# Mi2_v2.net
KiCad netlist of a schematic drawn in EAGLE
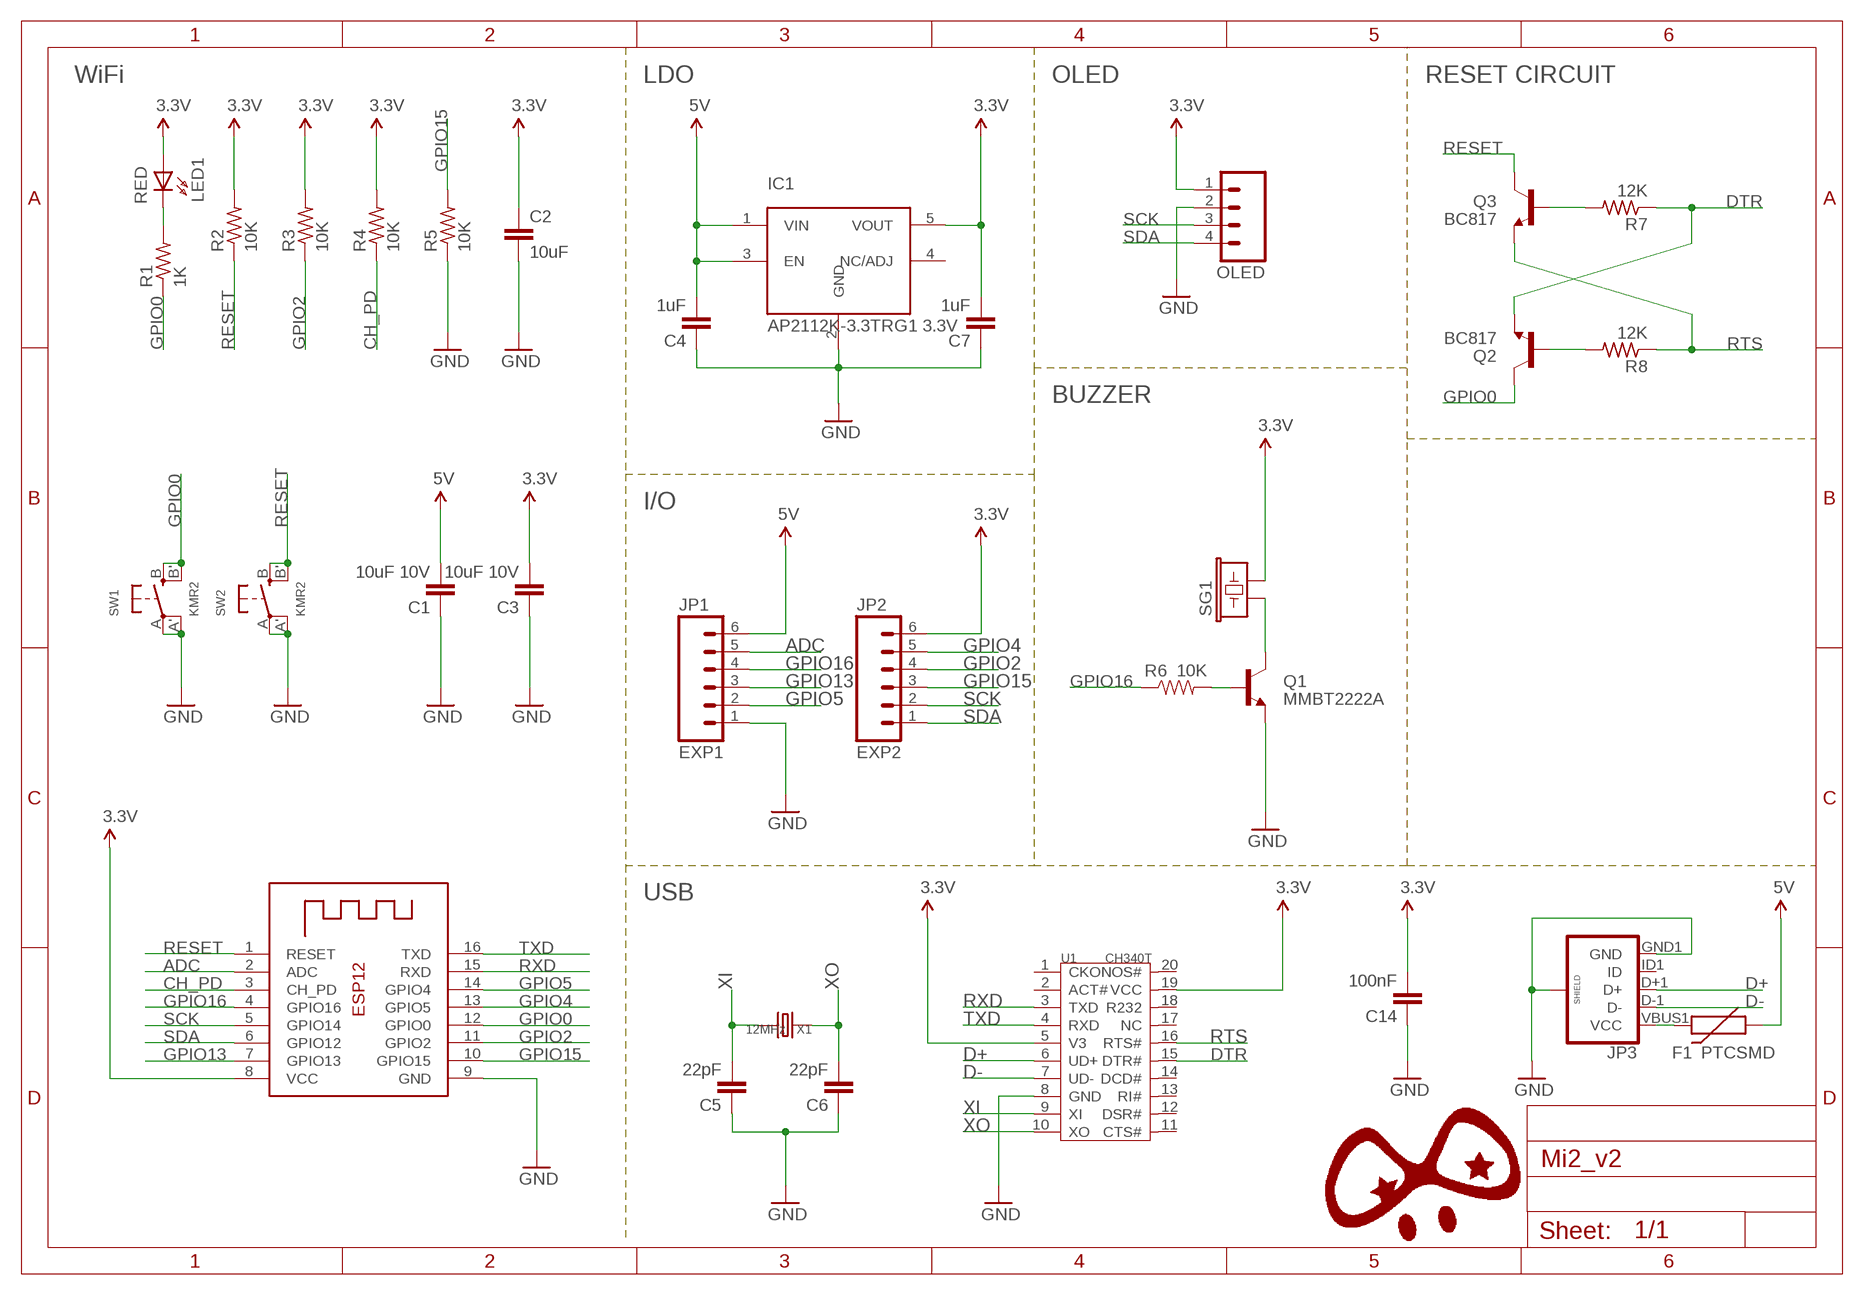
[diagram p0: schematic, sheet 1]

(export (version "E")
  (design (tool "Eeschema 10.0.6"))
  (components
    (comp (ref "C1")
      (value "10uF 10V")
      (footprint "eagle-import:0402-CAP")
      (libsource (lib "eagle-import") (part "CAP0402-CAP"))
    )
    (comp (ref "C2")
      (value "10uF")
      (footprint "eagle-import:0603-CAP")
      (libsource (lib "eagle-import") (part "10UF-6.3V-20%(0603)"))
    )
    (comp (ref "C3")
      (value "10uF 10V")
      (footprint "eagle-import:0402-CAP")
      (libsource (lib "eagle-import") (part "CAP0402-CAP"))
    )
    (comp (ref "C4")
      (value "1uF")
      (footprint "eagle-import:0402-CAP")
      (libsource (lib "eagle-import") (part "CAP0402-CAP"))
    )
    (comp (ref "C5")
      (value "22pF")
      (footprint "eagle-import:0402-CAP")
      (libsource (lib "eagle-import") (part "CAP0402-CAP"))
    )
    (comp (ref "C6")
      (value "22pF")
      (footprint "eagle-import:0402-CAP")
      (libsource (lib "eagle-import") (part "CAP0402-CAP"))
    )
    (comp (ref "C7")
      (value "1uF")
      (footprint "eagle-import:0402-CAP")
      (libsource (lib "eagle-import") (part "CAP0402-CAP"))
    )
    (comp (ref "C14")
      (value "100nF")
      (footprint "eagle-import:0402-CAP")
      (libsource (lib "eagle-import") (part "CAP0402-CAP"))
    )
    (comp (ref "F1")
      (value "PTCSMD")
      (footprint "eagle-import:PTC-1206")
      (libsource (lib "eagle-import") (part "PTCSMD"))
    )
    (comp (ref "IC1")
      (value "AP2112K-3.3TRG1 3.3V")
      (footprint "eagle-import:SOT23-5")
      (libsource (lib "eagle-import") (part "5PIN_REG"))
    )
    (comp (ref "JP1")
      (value "EXP1")
      (footprint "eagle-import:1X06_LOCK")
      (libsource (lib "eagle-import") (part "M06LOCK"))
    )
    (comp (ref "JP2")
      (value "EXP2")
      (footprint "eagle-import:1X06_LOCK")
      (libsource (lib "eagle-import") (part "M06LOCK"))
    )
    (comp (ref "JP3")
      (value "USB_MICROB_PLUGCONN-11752")
      (footprint "eagle-import:USB-B-MICRO-SMD_V03")
      (libsource (lib "eagle-import") (part "USB_MICROB_PLUGCONN-11752"))
    )
    (comp (ref "LED1")
      (value "RED")
      (footprint "eagle-import:LED-0603_L")
      (libsource (lib "eagle-import") (part "LED0603DWS_L"))
    )
    (comp (ref "OLED")
      (value "M04LOCK")
      (footprint "eagle-import:1X04_LOCK")
      (libsource (lib "eagle-import") (part "M04LOCK"))
    )
    (comp (ref "Q1")
      (value "MMBT2222A")
      (footprint "eagle-import:SOT23-3")
      (libsource (lib "eagle-import") (part "TRANSISTOR_NPNMMBT2222A"))
    )
    (comp (ref "Q2")
      (value "BC817")
      (footprint "eagle-import:SOT23-3")
      (libsource (lib "eagle-import") (part "TRANSISTOR_NPNMMBT2222A"))
    )
    (comp (ref "Q3")
      (value "BC817")
      (footprint "eagle-import:SOT23-3")
      (libsource (lib "eagle-import") (part "TRANSISTOR_NPNMMBT2222A"))
    )
    (comp (ref "R1")
      (value "1K")
      (footprint "eagle-import:R0402")
      (libsource (lib "eagle-import") (part "R-US_R0402"))
    )
    (comp (ref "R2")
      (value "10K")
      (footprint "eagle-import:R0402")
      (libsource (lib "eagle-import") (part "R-US_R0402"))
    )
    (comp (ref "R3")
      (value "10K")
      (footprint "eagle-import:R0402")
      (libsource (lib "eagle-import") (part "R-US_R0402"))
    )
    (comp (ref "R4")
      (value "10K")
      (footprint "eagle-import:R0402")
      (libsource (lib "eagle-import") (part "R-US_R0402"))
    )
    (comp (ref "R5")
      (value "10K")
      (footprint "eagle-import:R0402")
      (libsource (lib "eagle-import") (part "R-US_R0402"))
    )
    (comp (ref "R6")
      (value "10K")
      (footprint "eagle-import:0402-RES")
      (libsource (lib "eagle-import") (part "RESISTOR0402-RES"))
    )
    (comp (ref "R7")
      (value "12K")
      (footprint "eagle-import:R0402")
      (libsource (lib "eagle-import") (part "R-US_R0402"))
    )
    (comp (ref "R8")
      (value "12K")
      (footprint "eagle-import:R0402")
      (libsource (lib "eagle-import") (part "R-US_R0402"))
    )
    (comp (ref "SG1")
      (value "BUZZERSMD2")
      (footprint "eagle-import:BUZZER-CCV")
      (libsource (lib "eagle-import") (part "BUZZERSMD2"))
    )
    (comp (ref "SW1")
      (value "KMR2")
      (footprint "eagle-import:BTN_KMR2_4.6X2.8")
      (libsource (lib "eagle-import") (part "SWITCH_TACT_SMT4.6X2.8"))
    )
    (comp (ref "SW2")
      (value "KMR2")
      (footprint "eagle-import:BTN_KMR2_4.6X2.8")
      (libsource (lib "eagle-import") (part "SWITCH_TACT_SMT4.6X2.8"))
    )
    (comp (ref "U1")
      (value "CH340T")
      (footprint "eagle-import:SSOP20")
      (libsource (lib "eagle-import") (part "CH340T"))
    )
    (comp (ref "X1")
      (value "12MHz")
      (footprint "eagle-import:2P-SMD-5X3.2")
      (libsource (lib "eagle-import") (part "CRYSTAL'5032'"))
    )
    (comp (ref "X2")
      (value "ESP-12")
      (footprint "eagle-import:ESP-12")
      (libsource (lib "eagle-import") (part "ESP-12"))
    )
  )
  (nets
    (net (code "1") (name "/ADC") (class "Default")
      (node (ref "JP1") (pin "5") (pinfunction "5_5") (pintype "passive"))
      (node (ref "X2") (pin "2") (pinfunction "ADC_2") (pintype "passive"))
    )
    (net (code "2") (name "/CH_PD") (class "Default")
      (node (ref "R4") (pin "1") (pinfunction "1_1") (pintype "passive"))
      (node (ref "X2") (pin "3") (pinfunction "CH_PD_3") (pintype "input"))
    )
    (net (code "3") (name "/D+") (class "Default")
      (node (ref "JP3") (pin "D+1") (pinfunction "D+_D+1") (pintype "bidirectional"))
      (node (ref "U1") (pin "6") (pinfunction "UD+_6") (pintype "bidirectional"))
    )
    (net (code "4") (name "/D-") (class "Default")
      (node (ref "JP3") (pin "D-1") (pinfunction "D-_D-1") (pintype "bidirectional"))
      (node (ref "U1") (pin "7") (pinfunction "UD-_7") (pintype "bidirectional"))
    )
    (net (code "5") (name "/DTR") (class "Default")
      (node (ref "Q2") (pin "2") (pinfunction "E_2") (pintype "passive"))
      (node (ref "R7") (pin "1") (pinfunction "1_1") (pintype "passive"))
      (node (ref "U1") (pin "15") (pinfunction "DTR#_15") (pintype "output"))
    )
    (net (code "6") (name "/GPIO0") (class "Default")
      (node (ref "Q2") (pin "3") (pinfunction "C_3") (pintype "passive"))
      (node (ref "R1") (pin "1") (pinfunction "1_1") (pintype "passive"))
      (node (ref "SW1") (pin "B") (pinfunction "S_B") (pintype "passive"))
      (node (ref "SW1") (pin "B'") (pinfunction "S1_B'") (pintype "passive"))
      (node (ref "X2") (pin "12") (pinfunction "GPIO0_12") (pintype "bidirectional"))
    )
    (net (code "7") (name "/GPIO2") (class "Default")
      (node (ref "JP2") (pin "4") (pinfunction "4_4") (pintype "passive"))
      (node (ref "R3") (pin "1") (pinfunction "1_1") (pintype "passive"))
      (node (ref "X2") (pin "11") (pinfunction "GPIO2_11") (pintype "bidirectional"))
    )
    (net (code "8") (name "/GPIO4") (class "Default")
      (node (ref "JP2") (pin "5") (pinfunction "5_5") (pintype "passive"))
      (node (ref "X2") (pin "13") (pinfunction "GPIO5_13") (pintype "bidirectional"))
    )
    (net (code "9") (name "/GPIO5") (class "Default")
      (node (ref "JP1") (pin "2") (pinfunction "2_2") (pintype "passive"))
      (node (ref "X2") (pin "14") (pinfunction "GPIO4_14") (pintype "bidirectional"))
    )
    (net (code "10") (name "/GPIO13") (class "Default")
      (node (ref "JP1") (pin "3") (pinfunction "3_3") (pintype "passive"))
      (node (ref "X2") (pin "7") (pinfunction "GPIO13_7") (pintype "bidirectional"))
    )
    (net (code "11") (name "/GPIO15") (class "Default")
      (node (ref "JP2") (pin "3") (pinfunction "3_3") (pintype "passive"))
      (node (ref "R5") (pin "2") (pinfunction "2_2") (pintype "passive"))
      (node (ref "X2") (pin "10") (pinfunction "GPIO15_10") (pintype "bidirectional"))
    )
    (net (code "12") (name "/GPIO16") (class "Default")
      (node (ref "JP1") (pin "4") (pinfunction "4_4") (pintype "passive"))
      (node (ref "R6") (pin "1") (pinfunction "1_1") (pintype "passive"))
      (node (ref "X2") (pin "4") (pinfunction "GPIO16_4") (pintype "bidirectional"))
    )
    (net (code "13") (name "/NOS#") (class "Default")
      (node (ref "U1") (pin "20") (pinfunction "NOS#_20") (pintype "power_in"))
    )
    (net (code "14") (name "/RESET") (class "Default")
      (node (ref "Q3") (pin "3") (pinfunction "C_3") (pintype "passive"))
      (node (ref "R2") (pin "1") (pinfunction "1_1") (pintype "passive"))
      (node (ref "SW2") (pin "B") (pinfunction "S_B") (pintype "passive"))
      (node (ref "SW2") (pin "B'") (pinfunction "S1_B'") (pintype "passive"))
      (node (ref "X2") (pin "1") (pinfunction "RESET_1") (pintype "input"))
    )
    (net (code "15") (name "/RTS") (class "Default")
      (node (ref "Q3") (pin "2") (pinfunction "E_2") (pintype "passive"))
      (node (ref "R8") (pin "1") (pinfunction "1_1") (pintype "passive"))
      (node (ref "U1") (pin "16") (pinfunction "RTS#_16") (pintype "output"))
    )
    (net (code "16") (name "/RXD") (class "Default")
      (node (ref "U1") (pin "3") (pinfunction "TXD_3") (pintype "output"))
      (node (ref "X2") (pin "15") (pinfunction "RXD_15") (pintype "input"))
    )
    (net (code "17") (name "/SCK") (class "Default")
      (node (ref "JP2") (pin "2") (pinfunction "2_2") (pintype "passive"))
      (node (ref "OLED") (pin "3") (pinfunction "3_3") (pintype "passive"))
      (node (ref "X2") (pin "5") (pinfunction "GPIO14_5") (pintype "bidirectional"))
    )
    (net (code "18") (name "/SDA") (class "Default")
      (node (ref "JP2") (pin "1") (pinfunction "1_1") (pintype "passive"))
      (node (ref "OLED") (pin "4") (pinfunction "4_4") (pintype "passive"))
      (node (ref "X2") (pin "6") (pinfunction "GPIO12_6") (pintype "bidirectional"))
    )
    (net (code "19") (name "/TXD") (class "Default")
      (node (ref "U1") (pin "4") (pinfunction "RXD_4") (pintype "input"))
      (node (ref "X2") (pin "16") (pinfunction "TXD_16") (pintype "output"))
    )
    (net (code "20") (name "/XI") (class "Default")
      (node (ref "C5") (pin "2") (pinfunction "2_2") (pintype "passive"))
      (node (ref "U1") (pin "9") (pinfunction "XI_9") (pintype "input"))
      (node (ref "X1") (pin "2") (pinfunction "2_2") (pintype "passive"))
    )
    (net (code "21") (name "/XO") (class "Default")
      (node (ref "C6") (pin "2") (pinfunction "2_2") (pintype "passive"))
      (node (ref "U1") (pin "10") (pinfunction "XO_10") (pintype "output"))
      (node (ref "X1") (pin "1") (pinfunction "1_1") (pintype "passive"))
    )
    (net (code "22") (name "3.3V") (class "Default")
      (node (ref "C14") (pin "2") (pinfunction "2_2") (pintype "passive"))
      (node (ref "C2") (pin "1") (pinfunction "1_1") (pintype "passive"))
      (node (ref "C3") (pin "2") (pinfunction "2_2") (pintype "passive"))
      (node (ref "C7") (pin "2") (pinfunction "2_2") (pintype "passive"))
      (node (ref "IC1") (pin "5") (pinfunction "VOUT_5") (pintype "bidirectional"))
      (node (ref "JP2") (pin "6") (pinfunction "6_6") (pintype "passive"))
      (node (ref "LED1") (pin "A") (pinfunction "A_A") (pintype "passive"))
      (node (ref "OLED") (pin "1") (pinfunction "1_1") (pintype "passive"))
      (node (ref "R2") (pin "2") (pinfunction "2_2") (pintype "passive"))
      (node (ref "R3") (pin "2") (pinfunction "2_2") (pintype "passive"))
      (node (ref "R4") (pin "2") (pinfunction "2_2") (pintype "passive"))
      (node (ref "SG1") (pin "-") (pinfunction "2_-") (pintype "passive"))
      (node (ref "U1") (pin "19") (pinfunction "VCC_19") (pintype "power_in"))
      (node (ref "U1") (pin "5") (pinfunction "V3_5") (pintype "power_in"))
      (node (ref "X2") (pin "8") (pinfunction "VCC_8") (pintype "power_in"))
    )
    (net (code "23") (name "5V") (class "Default")
      (node (ref "C1") (pin "2") (pinfunction "2_2") (pintype "passive"))
      (node (ref "C4") (pin "2") (pinfunction "2_2") (pintype "passive"))
      (node (ref "F1") (pin "1") (pinfunction "1_1") (pintype "bidirectional"))
      (node (ref "IC1") (pin "1") (pinfunction "VIN_1") (pintype "bidirectional"))
      (node (ref "IC1") (pin "3") (pinfunction "EN_3") (pintype "bidirectional"))
      (node (ref "JP1") (pin "6") (pinfunction "6_6") (pintype "passive"))
    )
    (net (code "24") (name "GND") (class "Default")
      (node (ref "C1") (pin "1") (pinfunction "1_1") (pintype "passive"))
      (node (ref "C14") (pin "1") (pinfunction "1_1") (pintype "passive"))
      (node (ref "C2") (pin "2") (pinfunction "2_2") (pintype "passive"))
      (node (ref "C3") (pin "1") (pinfunction "1_1") (pintype "passive"))
      (node (ref "C4") (pin "1") (pinfunction "1_1") (pintype "passive"))
      (node (ref "C5") (pin "1") (pinfunction "1_1") (pintype "passive"))
      (node (ref "C6") (pin "1") (pinfunction "1_1") (pintype "passive"))
      (node (ref "C7") (pin "1") (pinfunction "1_1") (pintype "passive"))
      (node (ref "IC1") (pin "2") (pinfunction "GND_2") (pintype "bidirectional"))
      (node (ref "JP1") (pin "1") (pinfunction "1_1") (pintype "passive"))
      (node (ref "JP3") (pin "GND1") (pinfunction "GND_GND1") (pintype "bidirectional"))
      (node (ref "JP3") (pin "SHIELD1") (pinfunction "SHIELD_SHIELD1") (pintype "bidirectional"))
      (node (ref "JP3") (pin "SHIELD2") (pinfunction "SHIELD_SHIELD2") (pintype "bidirectional"))
      (node (ref "JP3") (pin "SHIELD3") (pinfunction "SHIELD_SHIELD3") (pintype "bidirectional"))
      (node (ref "OLED") (pin "2") (pinfunction "2_2") (pintype "passive"))
      (node (ref "Q1") (pin "2") (pinfunction "E_2") (pintype "passive"))
      (node (ref "R5") (pin "1") (pinfunction "1_1") (pintype "passive"))
      (node (ref "SW1") (pin "A") (pinfunction "P_A") (pintype "passive"))
      (node (ref "SW1") (pin "A'") (pinfunction "P1_A'") (pintype "passive"))
      (node (ref "SW2") (pin "A") (pinfunction "P_A") (pintype "passive"))
      (node (ref "SW2") (pin "A'") (pinfunction "P1_A'") (pintype "passive"))
      (node (ref "U1") (pin "8") (pinfunction "GND_8") (pintype "power_in"))
      (node (ref "X2") (pin "9") (pinfunction "GND_9") (pintype "power_in"))
    )
    (net (code "25") (name "Net-(JP3-VCC)") (class "Default")
      (node (ref "F1") (pin "2") (pinfunction "2_2") (pintype "bidirectional"))
      (node (ref "JP3") (pin "VBUS1") (pinfunction "VCC_VBUS1") (pintype "bidirectional"))
    )
    (net (code "26") (name "Net-(LED1-PadC)") (class "Default")
      (node (ref "LED1") (pin "C") (pinfunction "C_C") (pintype "passive"))
      (node (ref "R1") (pin "2") (pinfunction "2_2") (pintype "passive"))
    )
    (net (code "27") (name "Net-(Q1-B)") (class "Default")
      (node (ref "Q1") (pin "1") (pinfunction "B_1") (pintype "passive"))
      (node (ref "R6") (pin "2") (pinfunction "2_2") (pintype "passive"))
    )
    (net (code "28") (name "Net-(Q1-C)") (class "Default")
      (node (ref "Q1") (pin "3") (pinfunction "C_3") (pintype "passive"))
      (node (ref "SG1") (pin "+") (pinfunction "1_+") (pintype "passive"))
    )
    (net (code "29") (name "Net-(Q2-B)") (class "Default")
      (node (ref "Q2") (pin "1") (pinfunction "B_1") (pintype "passive"))
      (node (ref "R8") (pin "2") (pinfunction "2_2") (pintype "passive"))
    )
    (net (code "30") (name "Net-(Q3-B)") (class "Default")
      (node (ref "Q3") (pin "1") (pinfunction "B_1") (pintype "passive"))
      (node (ref "R7") (pin "2") (pinfunction "2_2") (pintype "passive"))
    )
    (net (code "31") (name "unconnected-(IC1-NC{slash}ADJ-Pad4)") (class "Default")
      (node (ref "IC1") (pin "4") (pinfunction "NC/ADJ_4") (pintype "bidirectional"))
    )
    (net (code "32") (name "unconnected-(JP3-ID-PadID1)") (class "Default")
      (node (ref "JP3") (pin "ID1") (pinfunction "ID_ID1") (pintype "bidirectional"))
    )
    (net (code "33") (name "unconnected-(U1-ACT#-Pad2)") (class "Default")
      (node (ref "U1") (pin "2") (pinfunction "ACT#_2") (pintype "output"))
    )
    (net (code "34") (name "unconnected-(U1-CKO-Pad1)") (class "Default")
      (node (ref "U1") (pin "1") (pinfunction "CKO_1") (pintype "output"))
    )
    (net (code "35") (name "unconnected-(U1-CTS#-Pad11)") (class "Default")
      (node (ref "U1") (pin "11") (pinfunction "CTS#_11") (pintype "input"))
    )
    (net (code "36") (name "unconnected-(U1-DCD#-Pad14)") (class "Default")
      (node (ref "U1") (pin "14") (pinfunction "DCD#_14") (pintype "input"))
    )
    (net (code "37") (name "unconnected-(U1-DSR#-Pad12)") (class "Default")
      (node (ref "U1") (pin "12") (pinfunction "DSR#_12") (pintype "input"))
    )
    (net (code "38") (name "unconnected-(U1-NC-Pad17)") (class "Default")
      (node (ref "U1") (pin "17") (pinfunction "NC_17") (pintype "no_connect"))
    )
    (net (code "39") (name "unconnected-(U1-R232-Pad18)") (class "Default")
      (node (ref "U1") (pin "18") (pinfunction "R232_18") (pintype "input"))
    )
    (net (code "40") (name "unconnected-(U1-RI#-Pad13)") (class "Default")
      (node (ref "U1") (pin "13") (pinfunction "RI#_13") (pintype "input"))
    )
  )
)
